# PiezoPreamp_V4.net
KiCad netlist of a schematic drawn in EAGLE
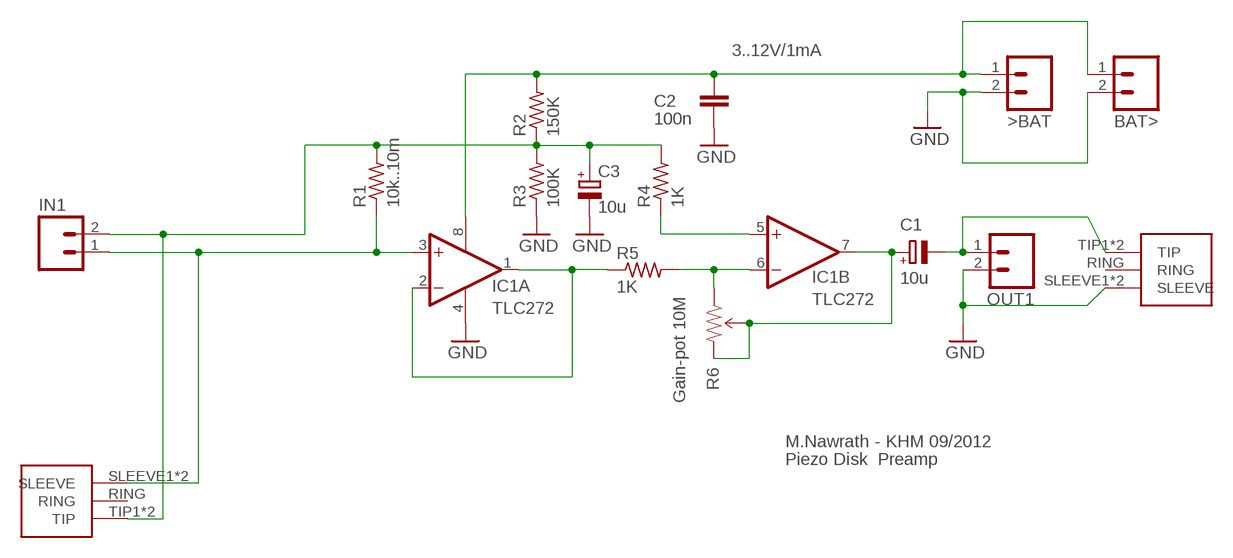
[diagram p0: schematic, sheet 1]

(export (version "E")
  (design (tool "Eeschema 10.0.6"))
  (components
    (comp (ref ">BAT")
      (value "M02LOCK")
      (footprint "eagle-import:1X02_LOCK")
      (libsource (lib "eagle-import") (part "M02LOCK"))
    )
    (comp (ref "BAT>")
      (value "M02LOCK")
      (footprint "eagle-import:1X02_LOCK")
      (libsource (lib "eagle-import") (part "M02LOCK"))
    )
    (comp (ref "C1")
      (value "10u")
      (footprint "eagle-import:E2,5-5")
      (libsource (lib "eagle-import") (part "CPOL-EUE2.5-5"))
    )
    (comp (ref "C2")
      (value "100n")
      (footprint "eagle-import:C025-025X050")
      (libsource (lib "eagle-import") (part "C-EU025-025X050"))
    )
    (comp (ref "C3")
      (value "10u")
      (footprint "eagle-import:E2,5-5")
      (libsource (lib "eagle-import") (part "CPOL-EUE2.5-5"))
    )
    (comp (ref "IC1")
      (value "TLC272")
      (footprint "eagle-import:DIL08")
      (libsource (lib "eagle-import") (part "TLC272P"))
    )
    (comp (ref "IN1")
      (value "M02LOCK")
      (footprint "eagle-import:1X02_LOCK")
      (libsource (lib "eagle-import") (part "M02LOCK"))
    )
    (comp (ref "OUT1")
      (value "M02LOCK")
      (footprint "eagle-import:1X02_LOCK")
      (libsource (lib "eagle-import") (part "M02LOCK"))
    )
    (comp (ref "OUT1-TRS")
      (value "1/8\"-F-STEREO-PCB")
      (footprint "eagle-import:1_8_-F-STEREO-PCB")
      (libsource (lib "eagle-import") (part "1/8{dblquote}-F-STEREO-PCB"))
    )
    (comp (ref "R1")
      (value "10k..10m")
      (footprint "eagle-import:0204V")
      (libsource (lib "eagle-import") (part "R-US_0204/2V"))
    )
    (comp (ref "R2")
      (value "150K")
      (footprint "eagle-import:0204V")
      (libsource (lib "eagle-import") (part "R-US_0204/2V"))
    )
    (comp (ref "R3")
      (value "100K")
      (footprint "eagle-import:0204V")
      (libsource (lib "eagle-import") (part "R-US_0204/2V"))
    )
    (comp (ref "R4")
      (value "1K")
      (footprint "eagle-import:0204V")
      (libsource (lib "eagle-import") (part "R-US_0204/2V"))
    )
    (comp (ref "R5")
      (value "1K")
      (footprint "eagle-import:0204V")
      (libsource (lib "eagle-import") (part "R-US_0204/2V"))
    )
    (comp (ref "R6")
      (value "Gain-pot 10M")
      (footprint "eagle-import:3386U")
      (libsource (lib "eagle-import") (part "TRIMPOT-PTH-KNOB"))
    )
    (comp (ref "U$2")
      (value "1/8\"-F-STEREO-PCB")
      (footprint "eagle-import:1_8_-F-STEREO-PCB")
      (libsource (lib "eagle-import") (part "1/8{dblquote}-F-STEREO-PCB"))
    )
  )
  (nets
    (net (code "1") (name "GND") (class "Default")
      (node (ref ">BAT") (pin "2") (pinfunction "2_2") (pintype "passive"))
      (node (ref "BAT>") (pin "2") (pinfunction "2_2") (pintype "passive"))
      (node (ref "C2") (pin "1") (pinfunction "1_1") (pintype "passive"))
      (node (ref "C3") (pin "-") (pinfunction "-_-") (pintype "passive"))
      (node (ref "IC1") (pin "4") (pinfunction "V-_4") (pintype "power_in"))
      (node (ref "OUT1") (pin "2") (pinfunction "2_2") (pintype "passive"))
      (node (ref "OUT1-TRS") (pin "SLEEVE1") (pinfunction "SLEEVE_SLEEVE1") (pintype "bidirectional"))
      (node (ref "OUT1-TRS") (pin "SLEEVE2") (pinfunction "SLEEVE_SLEEVE2") (pintype "bidirectional"))
      (node (ref "R3") (pin "1") (pinfunction "1_1") (pintype "passive"))
    )
    (net (code "2") (name "Net-(C1-Pad-)") (class "Default")
      (node (ref "C1") (pin "-") (pinfunction "-_-") (pintype "passive"))
      (node (ref "OUT1") (pin "1") (pinfunction "1_1") (pintype "passive"))
      (node (ref "OUT1-TRS") (pin "TIP1") (pinfunction "TIP_TIP1") (pintype "bidirectional"))
      (node (ref "OUT1-TRS") (pin "TIP2") (pinfunction "TIP_TIP2") (pintype "bidirectional"))
    )
    (net (code "3") (name "Net-(C3-Pad+)") (class "Default")
      (node (ref "C3") (pin "+") (pinfunction "+_+") (pintype "passive"))
      (node (ref "IN1") (pin "2") (pinfunction "2_2") (pintype "passive"))
      (node (ref "R1") (pin "2") (pinfunction "2_2") (pintype "passive"))
      (node (ref "R2") (pin "1") (pinfunction "1_1") (pintype "passive"))
      (node (ref "R3") (pin "2") (pinfunction "2_2") (pintype "passive"))
      (node (ref "R4") (pin "2") (pinfunction "2_2") (pintype "passive"))
      (node (ref "U$2") (pin "TIP1") (pinfunction "TIP_TIP1") (pintype "bidirectional"))
      (node (ref "U$2") (pin "TIP2") (pinfunction "TIP_TIP2") (pintype "bidirectional"))
    )
    (net (code "4") (name "Net-(IC1A-+IN)") (class "Default")
      (node (ref "IC1") (pin "3") (pinfunction "+IN_3") (pintype "input"))
      (node (ref "IN1") (pin "1") (pinfunction "1_1") (pintype "passive"))
      (node (ref "R1") (pin "1") (pinfunction "1_1") (pintype "passive"))
      (node (ref "U$2") (pin "SLEEVE1") (pinfunction "SLEEVE_SLEEVE1") (pintype "bidirectional"))
      (node (ref "U$2") (pin "SLEEVE2") (pinfunction "SLEEVE_SLEEVE2") (pintype "bidirectional"))
    )
    (net (code "5") (name "Net-(IC1A--IN)") (class "Default")
      (node (ref "IC1") (pin "1") (pinfunction "OUT_1") (pintype "output"))
      (node (ref "IC1") (pin "2") (pinfunction "-IN_2") (pintype "input"))
      (node (ref "R5") (pin "1") (pinfunction "1_1") (pintype "passive"))
    )
    (net (code "6") (name "Net-(IC1B-+IN)") (class "Default")
      (node (ref "IC1") (pin "5") (pinfunction "+IN_5") (pintype "input"))
      (node (ref "R4") (pin "1") (pinfunction "1_1") (pintype "passive"))
    )
    (net (code "7") (name "Net-(IC1B--IN)") (class "Default")
      (node (ref "IC1") (pin "6") (pinfunction "-IN_6") (pintype "input"))
      (node (ref "R5") (pin "2") (pinfunction "2_2") (pintype "passive"))
      (node (ref "R6") (pin "1") (pinfunction "CCW_1") (pintype "passive"))
    )
    (net (code "8") (name "Net-(IC1B-OUT)") (class "Default")
      (node (ref "C1") (pin "+") (pinfunction "+_+") (pintype "passive"))
      (node (ref "IC1") (pin "7") (pinfunction "OUT_7") (pintype "output"))
      (node (ref "R6") (pin "2") (pinfunction "WIPER_2") (pintype "passive"))
      (node (ref "R6") (pin "3") (pinfunction "CW_3") (pintype "passive"))
    )
    (net (code "9") (name "Net-(IC1C-V+)") (class "Default")
      (node (ref ">BAT") (pin "1") (pinfunction "1_1") (pintype "passive"))
      (node (ref "BAT>") (pin "1") (pinfunction "1_1") (pintype "passive"))
      (node (ref "C2") (pin "2") (pinfunction "2_2") (pintype "passive"))
      (node (ref "IC1") (pin "8") (pinfunction "V+_8") (pintype "power_in"))
      (node (ref "R2") (pin "2") (pinfunction "2_2") (pintype "passive"))
    )
    (net (code "10") (name "unconnected-(OUT1-TRS-PadRING)") (class "Default")
      (node (ref "OUT1-TRS") (pin "RING") (pinfunction "RING_RING") (pintype "bidirectional"))
    )
    (net (code "11") (name "unconnected-(U$2-PadRING)") (class "Default")
      (node (ref "U$2") (pin "RING") (pinfunction "RING_RING") (pintype "bidirectional"))
    )
  )
)
